# OpAmp_gain_stage.net
KiCad netlist of a schematic drawn in Altium Designer
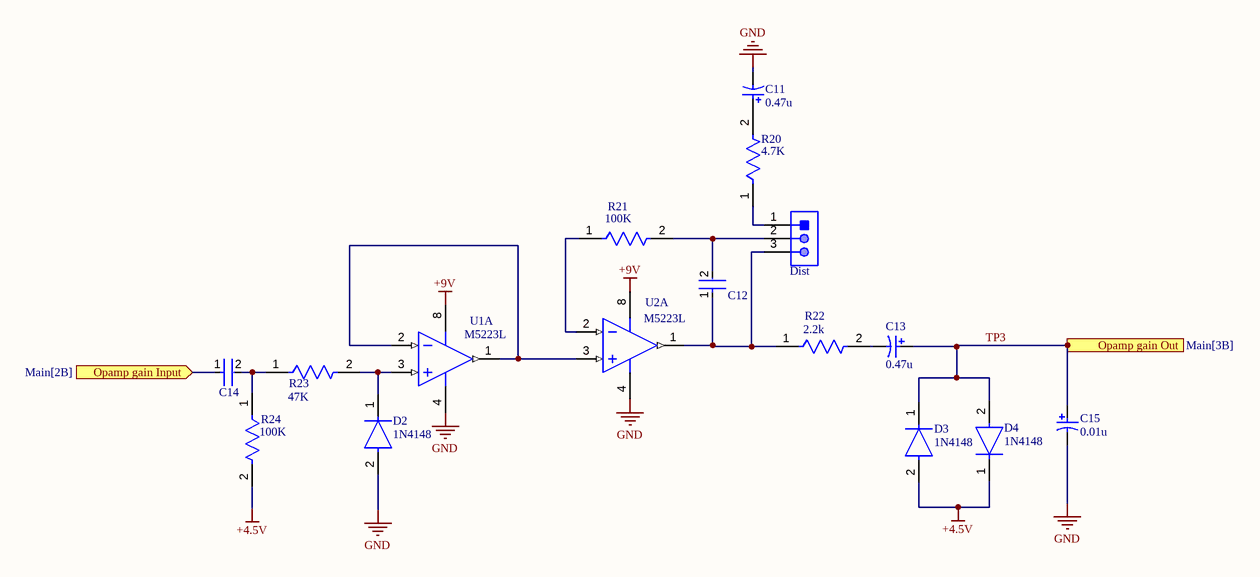
[diagram p0: OpAmp_gain stage.SchDoc]

(export (version "E")
  (design (tool "Eeschema 10.0.6"))
  (components
    (comp (ref "C11")
      (value "0.47u")
      (footprint "CAPPR55-200-1100X500X1200")
      (description "Aluminum Electrolytic Capacitor, 22 uF, +/- 20%, 50 V, -40 to 85 degC, 2-Pin THD, RoHS, Bulk")
      (fields (field (name "VOLTAGE") "50V") (field (name "MANUFACTURER") "Panasonic"))
      (libsource (lib "Altium Content Vault") (part "CAP-P-2"))
    )
    (comp (ref "C12")
      (value "100p")
      (footprint "FP-RCE1A2-MFG")
      (description "Cap Ceramic 100nF 100V X7R ±10% Radial 2.5mm +125°C Automotive Bulk")
      (fields (field (name "TOLERANCE") "10%"))
      (libsource (lib "Altium Content Vault") (part "02cd4be3c70576c341d710602a673aa"))
    )
    (comp (ref "C13")
      (value "0.47u")
      (footprint "CAPPR55-200-1100X500X1200")
      (description "Aluminum Electrolytic Capacitor, 22 uF, +/- 20%, 50 V, -40 to 85 degC, 2-Pin THD, RoHS, Bulk")
      (fields (field (name "VOLTAGE") "50V") (field (name "MANUFACTURER") "Panasonic"))
      (libsource (lib "Altium Content Vault") (part "CAP-P-2"))
    )
    (comp (ref "C14")
      (value "68n")
      (footprint "FP-RCE1A2-MFG")
      (description "Cap Ceramic 100nF 100V X7R ±10% Radial 2.5mm +125°C Automotive Bulk")
      (fields (field (name "TOLERANCE") "10%"))
      (libsource (lib "Altium Content Vault") (part "02cd4be3c70576c341d710602a673aa"))
    )
    (comp (ref "C15")
      (value "0.01u")
      (footprint "CAPPR55-200-1100X500X1200")
      (description "Aluminum Electrolytic Capacitor, 22 uF, +/- 20%, 50 V, -40 to 85 degC, 2-Pin THD, RoHS, Bulk")
      (fields (field (name "VOLTAGE") "50V") (field (name "MANUFACTURER") "Panasonic"))
      (libsource (lib "Altium Content Vault") (part "CAP-P-2"))
    )
    (comp (ref "D2")
      (value "1N4148")
      (footprint "FP-1N4007-MFG")
      (description "Rectifier diode 1000 V 1 A DO-41, ,")
      (fields (field (name "MANUFACTURER PART NUMBER") "1N4007") (field (name "MANUFACTURER") "Diotec"))
      (libsource (lib "Altium Content Vault") (part "d7152d700b627762746794eb795d46e"))
    )
    (comp (ref "D3")
      (value "1N4148")
      (footprint "FP-1N4007-MFG")
      (description "Rectifier diode 1000 V 1 A DO-41, ,")
      (fields (field (name "MANUFACTURER PART NUMBER") "1N4007") (field (name "MANUFACTURER") "Diotec"))
      (libsource (lib "Altium Content Vault") (part "d7152d700b627762746794eb795d46e"))
    )
    (comp (ref "D4")
      (value "1N4148")
      (footprint "FP-1N4007-MFG")
      (description "Rectifier diode 1000 V 1 A DO-41, ,")
      (fields (field (name "MANUFACTURER PART NUMBER") "1N4007") (field (name "MANUFACTURER") "Diotec"))
      (libsource (lib "Altium Content Vault") (part "d7152d700b627762746794eb795d46e"))
    )
    (comp (ref "Dist")
      (value "100K")
      (footprint "TECO-171825-3_V")
      (fields (field (name "MANUFACTURER") "TE Connectivity"))
      (libsource (lib "Altium Content Vault") (part "CN-1P-M-R3"))
    )
    (comp (ref "R20")
      (value "4.7K")
      (footprint "FP-MRS1600-MFG")
      (description "RES 20K OHM 0.4W 1% AXIAL")
      (fields (field (name "TOLERANCE") "1%"))
      (libsource (lib "Altium Content Vault") (part "1029c3af85768c4190bb7ad29bc67b5"))
    )
    (comp (ref "R21")
      (value "100K")
      (footprint "FP-MRS1600-MFG")
      (description "RES 20K OHM 0.4W 1% AXIAL")
      (fields (field (name "TOLERANCE") "1%"))
      (libsource (lib "Altium Content Vault") (part "1029c3af85768c4190bb7ad29bc67b5"))
    )
    (comp (ref "R22")
      (value "2.2k")
      (footprint "FP-MRS1600-MFG")
      (description "RES 20K OHM 0.4W 1% AXIAL")
      (fields (field (name "TOLERANCE") "1%"))
      (libsource (lib "Altium Content Vault") (part "1029c3af85768c4190bb7ad29bc67b5"))
    )
    (comp (ref "R23")
      (value "47K")
      (footprint "FP-MRS1600-MFG")
      (description "RES 20K OHM 0.4W 1% AXIAL")
      (fields (field (name "TOLERANCE") "1%"))
      (libsource (lib "Altium Content Vault") (part "1029c3af85768c4190bb7ad29bc67b5"))
    )
    (comp (ref "R24")
      (value "100K")
      (footprint "FP-MRS1600-MFG")
      (description "RES 20K OHM 0.4W 1% AXIAL")
      (fields (field (name "TOLERANCE") "1%"))
      (libsource (lib "Altium Content Vault") (part "1029c3af85768c4190bb7ad29bc67b5"))
    )
    (comp (ref "U1")
      (value "M5223L")
      (footprint "SIP249W50P254L2281H508Q9")
      (libsource (lib "Schlib1") (part "Component_1"))
    )
    (comp (ref "U2")
      (value "M5223L")
      (footprint "SIP249W50P254L2281H508Q9")
      (libsource (lib "Schlib1") (part "Component_1"))
    )
  )
  (nets
    (net (code "1") (name "+4.5V") (class "Default")
      (node (ref "D3") (pin "2") (pinfunction "A_2") (pintype "passive"))
      (node (ref "D4") (pin "1") (pinfunction "C_1") (pintype "passive"))
      (node (ref "R24") (pin "2") (pinfunction "2_2") (pintype "passive"))
    )
    (net (code "2") (name "+9V") (class "Default")
      (node (ref "U1") (pin "8") (pinfunction "VDD_8") (pintype "power_in"))
      (node (ref "U2") (pin "8") (pinfunction "VDD_8") (pintype "power_in"))
    )
    (net (code "3") (name "/Opamp gain Input") (class "Default")
      (node (ref "C14") (pin "1") (pinfunction "1_1") (pintype "passive"))
    )
    (net (code "4") (name "/TP3") (class "Default")
      (node (ref "C13") (pin "1") (pinfunction "1_1") (pintype "passive"))
      (node (ref "C15") (pin "1") (pinfunction "1_1") (pintype "passive"))
      (node (ref "D3") (pin "1") (pinfunction "C_1") (pintype "passive"))
      (node (ref "D4") (pin "2") (pinfunction "A_2") (pintype "passive"))
    )
    (net (code "5") (name "GND") (class "Default")
      (node (ref "C11") (pin "2") (pinfunction "2_2") (pintype "passive"))
      (node (ref "C15") (pin "2") (pinfunction "2_2") (pintype "passive"))
      (node (ref "D2") (pin "2") (pinfunction "A_2") (pintype "passive"))
      (node (ref "U1") (pin "4") (pinfunction "VSS_4") (pintype "power_in"))
      (node (ref "U2") (pin "4") (pinfunction "VSS_4") (pintype "power_in"))
    )
    (net (code "6") (name "Net-(C11-Pad1)") (class "Default")
      (node (ref "C11") (pin "1") (pinfunction "1_1") (pintype "passive"))
      (node (ref "R20") (pin "2") (pinfunction "2_2") (pintype "passive"))
    )
    (net (code "7") (name "Net-(C12-Pad2)") (class "Default")
      (node (ref "C12") (pin "2") (pinfunction "2_2") (pintype "passive"))
      (node (ref "Dist") (pin "2") (pinfunction "2_2") (pintype "passive"))
      (node (ref "R21") (pin "2") (pinfunction "2_2") (pintype "passive"))
    )
    (net (code "8") (name "Net-(C13-Pad2)") (class "Default")
      (node (ref "C13") (pin "2") (pinfunction "2_2") (pintype "passive"))
      (node (ref "R22") (pin "2") (pinfunction "2_2") (pintype "passive"))
    )
    (net (code "9") (name "Net-(C14-Pad2)") (class "Default")
      (node (ref "C14") (pin "2") (pinfunction "2_2") (pintype "passive"))
      (node (ref "R23") (pin "1") (pinfunction "1_1") (pintype "passive"))
      (node (ref "R24") (pin "1") (pinfunction "1_1") (pintype "passive"))
    )
    (net (code "10") (name "Net-(D2-C)") (class "Default")
      (node (ref "D2") (pin "1") (pinfunction "C_1") (pintype "passive"))
      (node (ref "R23") (pin "2") (pinfunction "2_2") (pintype "passive"))
      (node (ref "U1") (pin "3") (pinfunction "VINA+_3") (pintype "input"))
    )
    (net (code "11") (name "Net-(Dist-Pad1)") (class "Default")
      (node (ref "Dist") (pin "1") (pinfunction "1_1") (pintype "passive"))
      (node (ref "R20") (pin "1") (pinfunction "1_1") (pintype "passive"))
    )
    (net (code "12") (name "Net-(U1A-VINA-)") (class "Default")
      (node (ref "U1") (pin "1") (pinfunction "VOUTA_1") (pintype "output"))
      (node (ref "U1") (pin "2") (pinfunction "VINA-_2") (pintype "input"))
      (node (ref "U2") (pin "3") (pinfunction "VINA+_3") (pintype "input"))
    )
    (net (code "13") (name "Net-(U2A-VINA-)") (class "Default")
      (node (ref "R21") (pin "1") (pinfunction "1_1") (pintype "passive"))
      (node (ref "U2") (pin "2") (pinfunction "VINA-_2") (pintype "input"))
    )
    (net (code "14") (name "Net-(U2A-VOUTA)") (class "Default")
      (node (ref "C12") (pin "1") (pinfunction "1_1") (pintype "passive"))
      (node (ref "Dist") (pin "3") (pinfunction "3_3") (pintype "passive"))
      (node (ref "R22") (pin "1") (pinfunction "1_1") (pintype "passive"))
      (node (ref "U2") (pin "1") (pinfunction "VOUTA_1") (pintype "output"))
    )
  )
)
